# Processor.net
KiCad netlist of a schematic drawn in Altium Designer
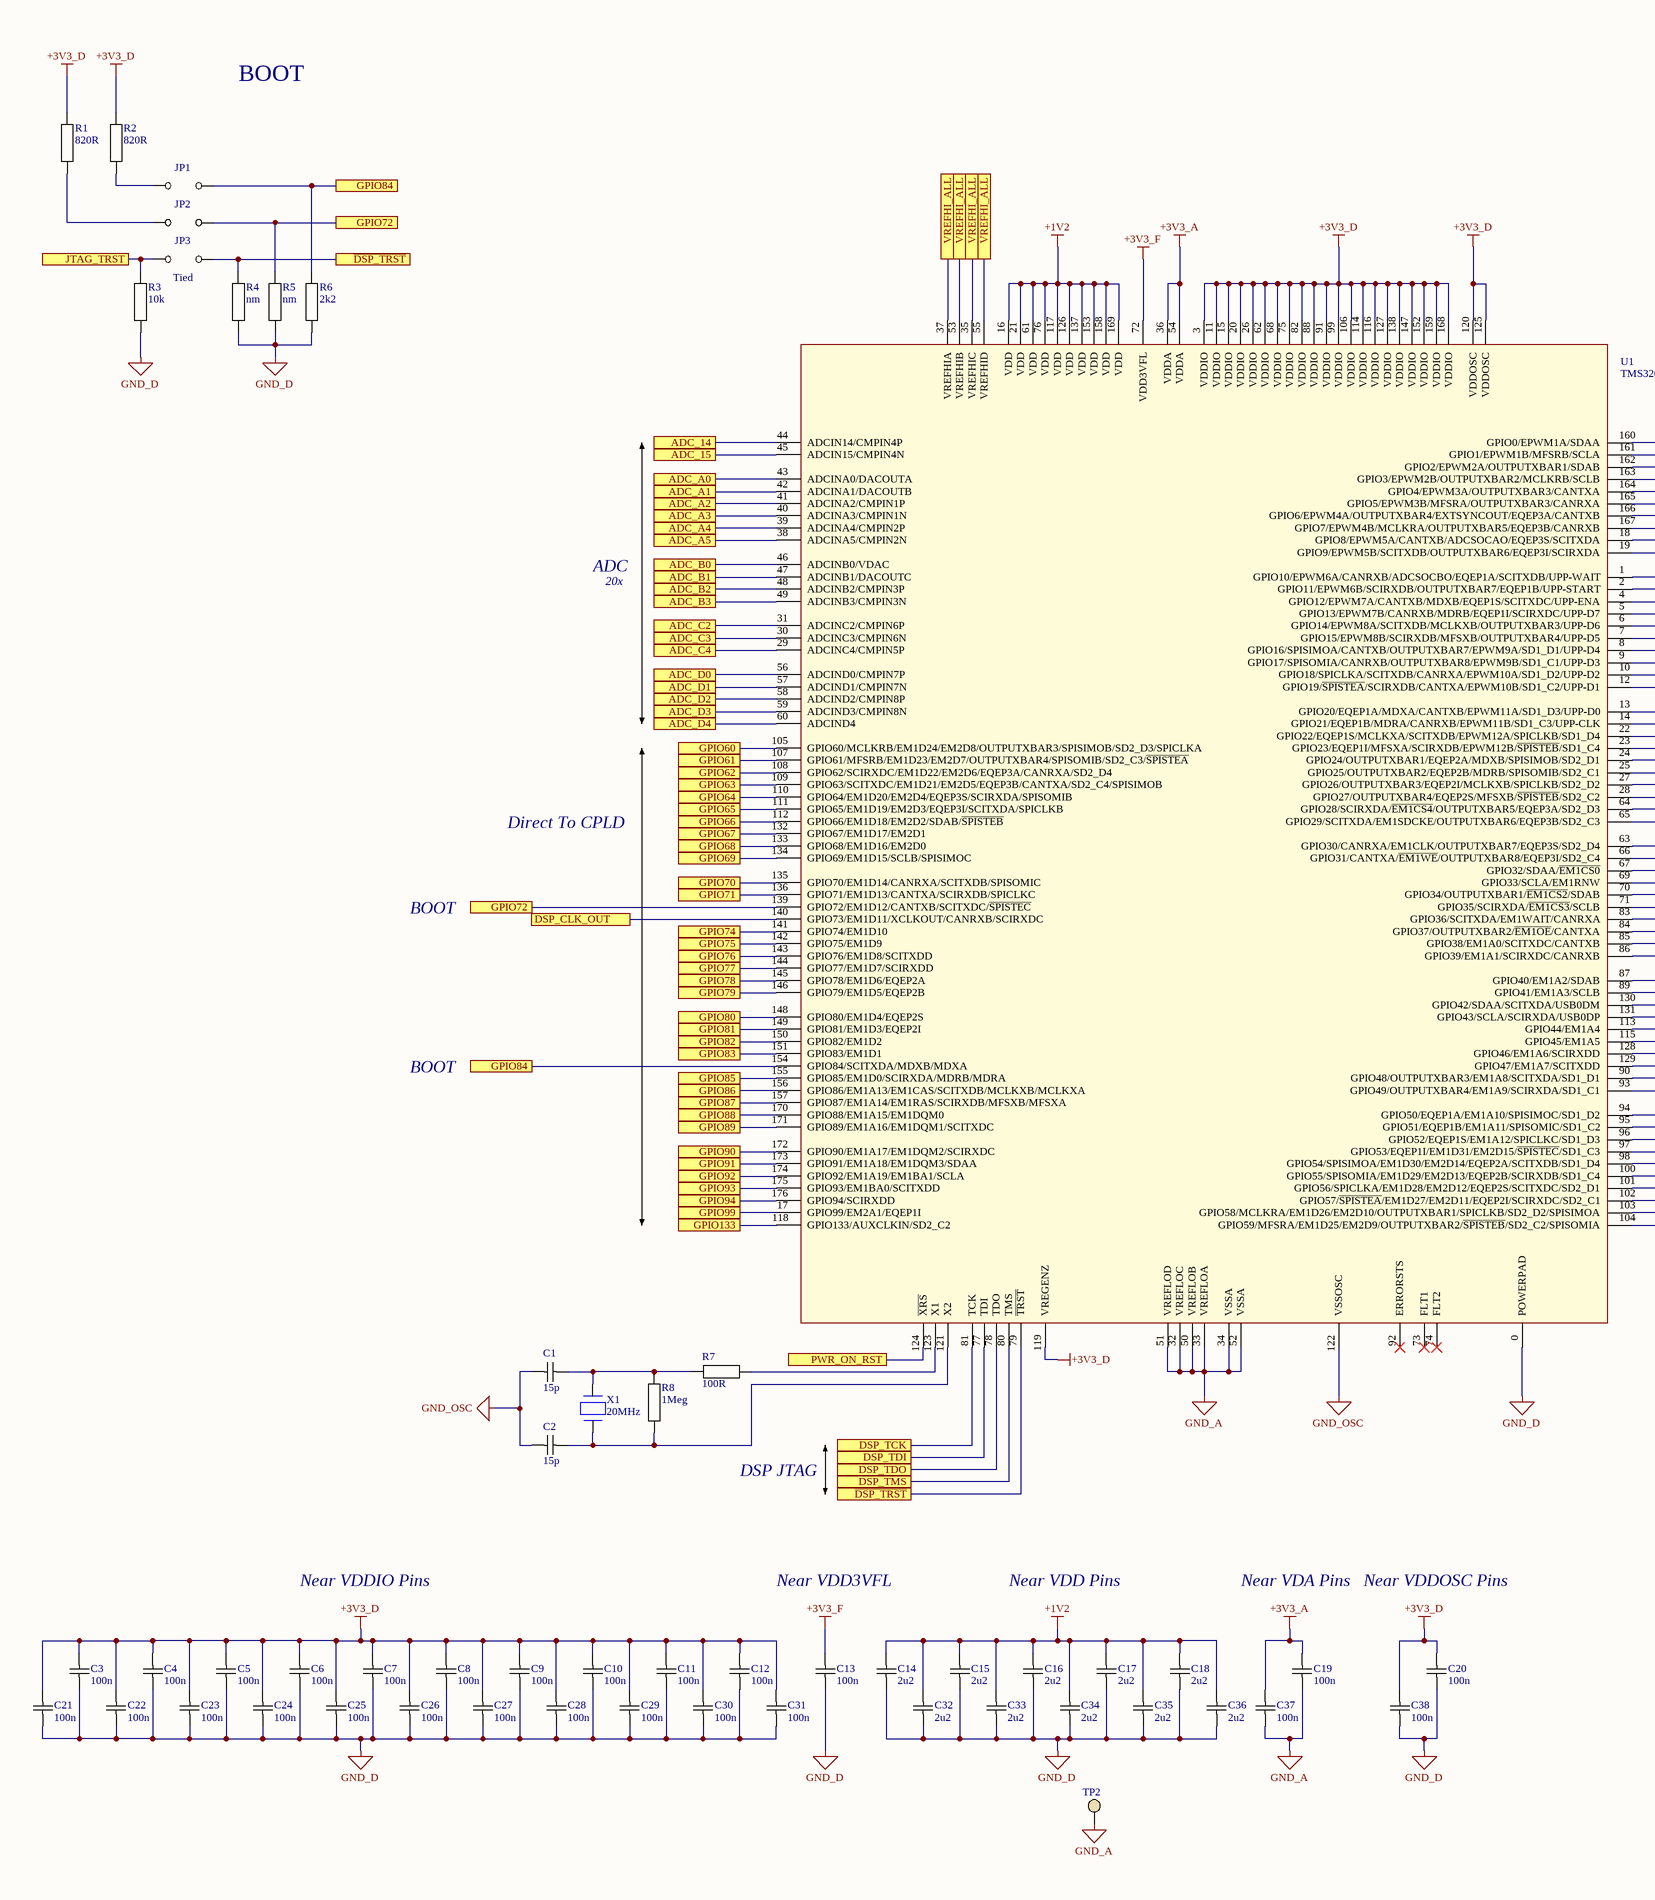
[diagram p0: Processor.SchDoc, left]
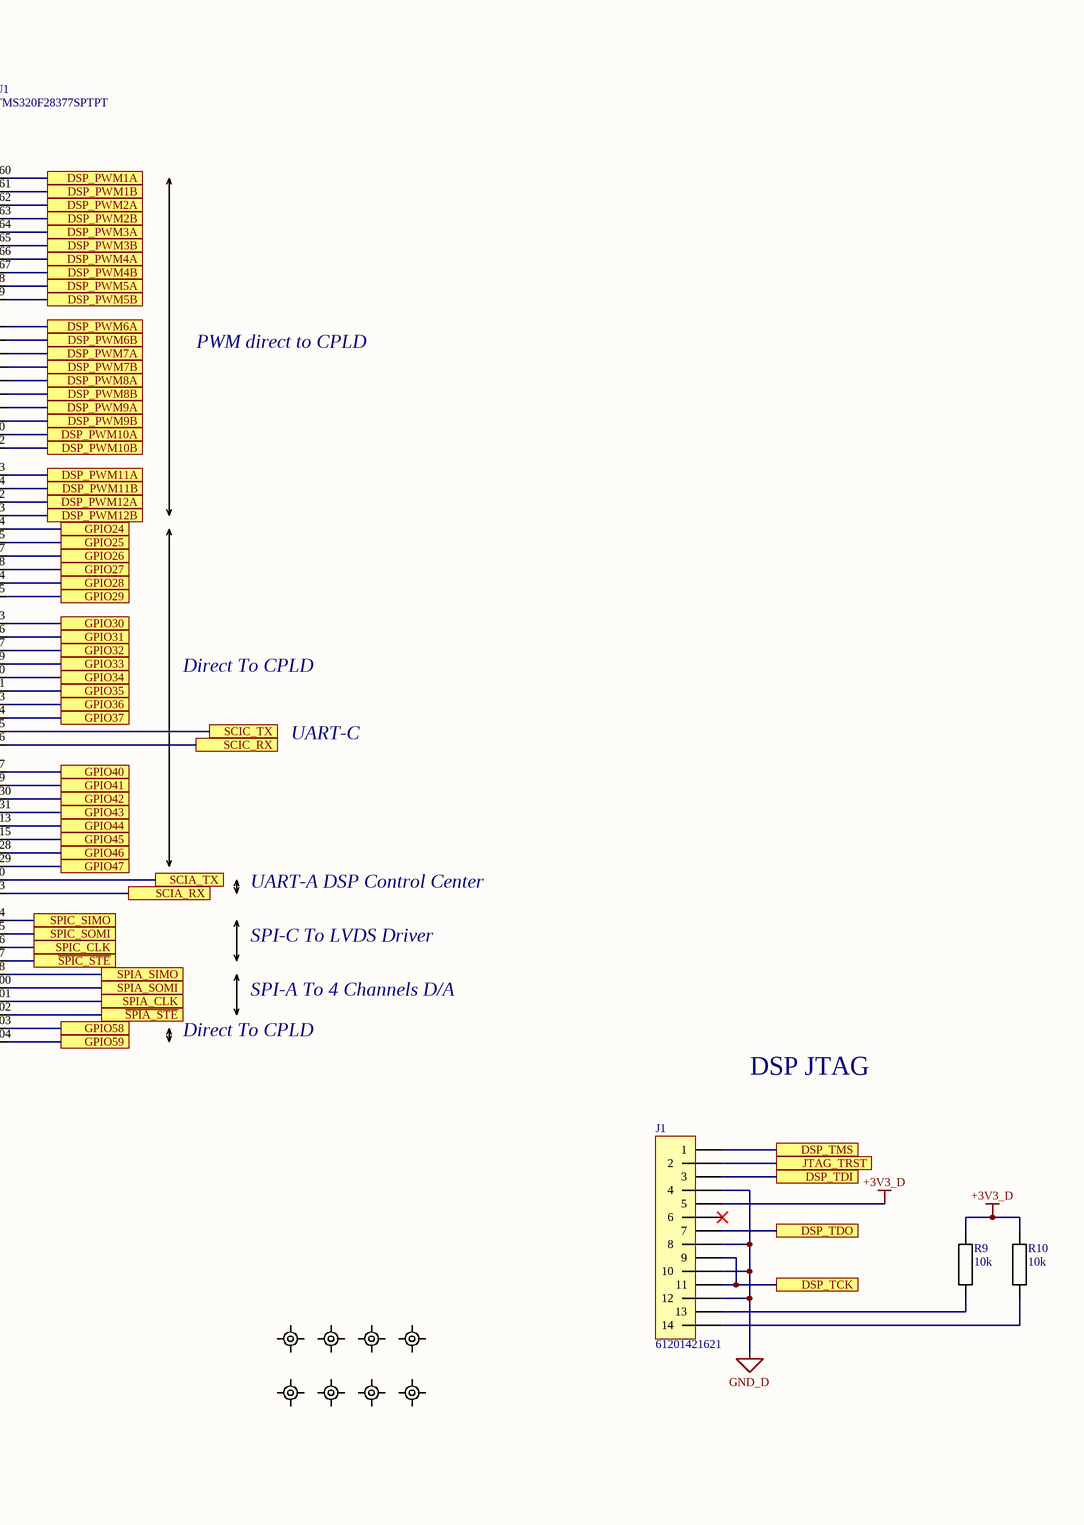
[diagram p1: Processor.SchDoc, right]

(export (version "E")
  (design (tool "Eeschema 10.0.6"))
  (components
    (comp (ref "C1")
      (value "15p")
      (footprint "CAPACITOR 1608 REFLOW")
      (description "Capacitor X7R 10% 50V 1608(0603)")
      (libsource (lib "Capacitor") (part "Capacitor"))
    )
    (comp (ref "C2")
      (value "15p")
      (footprint "CAPACITOR 1608 REFLOW")
      (description "Capacitor X7R 10% 50V 1608(0603)")
      (libsource (lib "Capacitor") (part "Capacitor"))
    )
    (comp (ref "C3")
      (value "100n")
      (footprint "CAPACITOR 1608 REFLOW")
      (description "Capacitor X7R 10% 50V 1608(0603)")
      (libsource (lib "Capacitor") (part "Capacitor"))
    )
    (comp (ref "C4")
      (value "100n")
      (footprint "CAPACITOR 1608 REFLOW")
      (description "Capacitor X7R 10% 50V 1608(0603)")
      (libsource (lib "Capacitor") (part "Capacitor"))
    )
    (comp (ref "C5")
      (value "100n")
      (footprint "CAPACITOR 1608 REFLOW")
      (description "Capacitor X7R 10% 50V 1608(0603)")
      (libsource (lib "Capacitor") (part "Capacitor"))
    )
    (comp (ref "C6")
      (value "100n")
      (footprint "CAPACITOR 1608 REFLOW")
      (description "Capacitor X7R 10% 50V 1608(0603)")
      (libsource (lib "Capacitor") (part "Capacitor"))
    )
    (comp (ref "C7")
      (value "100n")
      (footprint "CAPACITOR 1608 REFLOW")
      (description "Capacitor X7R 10% 50V 1608(0603)")
      (libsource (lib "Capacitor") (part "Capacitor"))
    )
    (comp (ref "C8")
      (value "100n")
      (footprint "CAPACITOR 1608 REFLOW")
      (description "Capacitor X7R 10% 50V 1608(0603)")
      (libsource (lib "Capacitor") (part "Capacitor"))
    )
    (comp (ref "C9")
      (value "100n")
      (footprint "CAPACITOR 1608 REFLOW")
      (description "Capacitor X7R 10% 50V 1608(0603)")
      (libsource (lib "Capacitor") (part "Capacitor"))
    )
    (comp (ref "C10")
      (value "100n")
      (footprint "CAPACITOR 1608 REFLOW")
      (description "Capacitor X7R 10% 50V 1608(0603)")
      (libsource (lib "Capacitor") (part "Capacitor"))
    )
    (comp (ref "C11")
      (value "100n")
      (footprint "CAPACITOR 1608 REFLOW")
      (description "Capacitor X7R 10% 50V 1608(0603)")
      (libsource (lib "Capacitor") (part "Capacitor"))
    )
    (comp (ref "C12")
      (value "100n")
      (footprint "CAPACITOR 1608 REFLOW")
      (description "Capacitor X7R 10% 50V 1608(0603)")
      (libsource (lib "Capacitor") (part "Capacitor"))
    )
    (comp (ref "C13")
      (value "100n")
      (footprint "CAPACITOR 1608 REFLOW")
      (description "Capacitor X7R 10% 50V 1608(0603)")
      (libsource (lib "Capacitor") (part "Capacitor"))
    )
    (comp (ref "C14")
      (value "2u2")
      (footprint "CAPACITOR 1608 REFLOW")
      (description "Capacitor X7R 10% 10V 1608(0603)")
      (libsource (lib "Capacitor") (part "Capacitor"))
    )
    (comp (ref "C15")
      (value "2u2")
      (footprint "CAPACITOR 1608 REFLOW")
      (description "Capacitor X7R 10% 10V 1608(0603)")
      (libsource (lib "Capacitor") (part "Capacitor"))
    )
    (comp (ref "C16")
      (value "2u2")
      (footprint "CAPACITOR 1608 REFLOW")
      (description "Capacitor X7R 10% 10V 1608(0603)")
      (libsource (lib "Capacitor") (part "Capacitor"))
    )
    (comp (ref "C17")
      (value "2u2")
      (footprint "CAPACITOR 1608 REFLOW")
      (description "Capacitor X7R 10% 10V 1608(0603)")
      (libsource (lib "Capacitor") (part "Capacitor"))
    )
    (comp (ref "C18")
      (value "2u2")
      (footprint "CAPACITOR 1608 REFLOW")
      (description "Capacitor X7R 10% 10V 1608(0603)")
      (libsource (lib "Capacitor") (part "Capacitor"))
    )
    (comp (ref "C19")
      (value "100n")
      (footprint "CAPACITOR 1608 REFLOW")
      (description "Capacitor X7R 10% 50V 1608(0603)")
      (libsource (lib "Capacitor") (part "Capacitor"))
    )
    (comp (ref "C20")
      (value "100n")
      (footprint "CAPACITOR 1608 REFLOW")
      (description "Capacitor X7R 10% 50V 1608(0603)")
      (libsource (lib "Capacitor") (part "Capacitor"))
    )
    (comp (ref "C21")
      (value "100n")
      (footprint "CAPACITOR 1608 REFLOW")
      (description "Capacitor X7R 10% 50V 1608(0603)")
      (libsource (lib "Capacitor") (part "Capacitor"))
    )
    (comp (ref "C22")
      (value "100n")
      (footprint "CAPACITOR 1608 REFLOW")
      (description "Capacitor X7R 10% 50V 1608(0603)")
      (libsource (lib "Capacitor") (part "Capacitor"))
    )
    (comp (ref "C23")
      (value "100n")
      (footprint "CAPACITOR 1608 REFLOW")
      (description "Capacitor X7R 10% 50V 1608(0603)")
      (libsource (lib "Capacitor") (part "Capacitor"))
    )
    (comp (ref "C24")
      (value "100n")
      (footprint "CAPACITOR 1608 REFLOW")
      (description "Capacitor X7R 10% 50V 1608(0603)")
      (libsource (lib "Capacitor") (part "Capacitor"))
    )
    (comp (ref "C25")
      (value "100n")
      (footprint "CAPACITOR 1608 REFLOW")
      (description "Capacitor X7R 10% 50V 1608(0603)")
      (libsource (lib "Capacitor") (part "Capacitor"))
    )
    (comp (ref "C26")
      (value "100n")
      (footprint "CAPACITOR 1608 REFLOW")
      (description "Capacitor X7R 10% 50V 1608(0603)")
      (libsource (lib "Capacitor") (part "Capacitor"))
    )
    (comp (ref "C27")
      (value "100n")
      (footprint "CAPACITOR 1608 REFLOW")
      (description "Capacitor X7R 10% 50V 1608(0603)")
      (libsource (lib "Capacitor") (part "Capacitor"))
    )
    (comp (ref "C28")
      (value "100n")
      (footprint "CAPACITOR 1608 REFLOW")
      (description "Capacitor X7R 10% 50V 1608(0603)")
      (libsource (lib "Capacitor") (part "Capacitor"))
    )
    (comp (ref "C29")
      (value "100n")
      (footprint "CAPACITOR 1608 REFLOW")
      (description "Capacitor X7R 10% 50V 1608(0603)")
      (libsource (lib "Capacitor") (part "Capacitor"))
    )
    (comp (ref "C30")
      (value "100n")
      (footprint "CAPACITOR 1608 REFLOW")
      (description "Capacitor X7R 10% 50V 1608(0603)")
      (libsource (lib "Capacitor") (part "Capacitor"))
    )
    (comp (ref "C31")
      (value "100n")
      (footprint "CAPACITOR 1608 REFLOW")
      (description "Capacitor X7R 10% 50V 1608(0603)")
      (libsource (lib "Capacitor") (part "Capacitor"))
    )
    (comp (ref "C32")
      (value "2u2")
      (footprint "CAPACITOR 1608 REFLOW")
      (description "Capacitor X7R 10% 10V 1608(0603)")
      (libsource (lib "Capacitor") (part "Capacitor"))
    )
    (comp (ref "C33")
      (value "2u2")
      (footprint "CAPACITOR 1608 REFLOW")
      (description "Capacitor X7R 10% 10V 1608(0603)")
      (libsource (lib "Capacitor") (part "Capacitor"))
    )
    (comp (ref "C34")
      (value "2u2")
      (footprint "CAPACITOR 1608 REFLOW")
      (description "Capacitor X7R 10% 10V 1608(0603)")
      (libsource (lib "Capacitor") (part "Capacitor"))
    )
    (comp (ref "C35")
      (value "2u2")
      (footprint "CAPACITOR 1608 REFLOW")
      (description "Capacitor X7R 10% 10V 1608(0603)")
      (libsource (lib "Capacitor") (part "Capacitor"))
    )
    (comp (ref "C36")
      (value "2u2")
      (footprint "CAPACITOR 1608 REFLOW")
      (description "Capacitor X7R 10% 10V 1608(0603)")
      (libsource (lib "Capacitor") (part "Capacitor"))
    )
    (comp (ref "C37")
      (value "100n")
      (footprint "CAPACITOR 1608 REFLOW")
      (description "Capacitor X7R 10% 50V 1608(0603)")
      (libsource (lib "Capacitor") (part "Capacitor"))
    )
    (comp (ref "C38")
      (value "100n")
      (footprint "CAPACITOR 1608 REFLOW")
      (description "Capacitor X7R 10% 50V 1608(0603)")
      (libsource (lib "Capacitor") (part "Capacitor"))
    )
    (comp (ref "J1")
      (value "61201421621")
      (footprint "FlatCable2x7 2.54MM Straight TH")
      (description "FlatCable2x7")
      (fields (field (name "MANUFACTURER") "Wurth Elektronik"))
      (libsource (lib "Connector") (part "FlatCable2x7"))
    )
    (comp (ref "JP1")
      (value "Tied")
      (footprint "JUMPER2 SMD 1608")
      (description "JUMPER 2 POS")
      (libsource (lib "Jumper") (part "JUMPER 2 POS"))
    )
    (comp (ref "JP2")
      (value "Tied")
      (footprint "JUMPER2 SMD 1608")
      (description "JUMPER 2 POS")
      (libsource (lib "Jumper") (part "JUMPER 2 POS"))
    )
    (comp (ref "JP3")
      (value "Tied")
      (footprint "JUMPER2 SMD 1608")
      (description "JUMPER 2 POS")
      (libsource (lib "Jumper") (part "JUMPER 2 POS"))
    )
    (comp (ref "R1")
      (value "820R")
      (footprint "RESISTOR 1608 REFLOW")
      (description "Resistor 1% 50V 100mW 1608(0603)")
      (libsource (lib "Resistor") (part "Resistor"))
    )
    (comp (ref "R2")
      (value "820R")
      (footprint "RESISTOR 1608 REFLOW")
      (description "Resistor 1% 50V 100mW 1608(0603)")
      (libsource (lib "Resistor") (part "Resistor"))
    )
    (comp (ref "R3")
      (value "10k")
      (footprint "RESISTOR 1608 REFLOW")
      (description "Resistor 1% 50V 100mW 1608(0603)")
      (libsource (lib "Resistor") (part "Resistor"))
    )
    (comp (ref "R4")
      (value "nm")
      (footprint "RESISTOR 1608 REFLOW")
      (description "Resistor 1% 50V 100mW 1608(0603)")
      (libsource (lib "Resistor") (part "Resistor"))
    )
    (comp (ref "R5")
      (value "nm")
      (footprint "RESISTOR 1608 REFLOW")
      (description "Resistor 1% 50V 100mW 1608(0603)")
      (libsource (lib "Resistor") (part "Resistor"))
    )
    (comp (ref "R6")
      (value "2k2")
      (footprint "RESISTOR 1608 REFLOW")
      (description "Resistor 1% 50V 100mW 1608(0603)")
      (libsource (lib "Resistor") (part "Resistor"))
    )
    (comp (ref "R7")
      (value "100R")
      (footprint "RESISTOR 1608 REFLOW")
      (description "Resistor 1% 50V 100mW 1608(0603)")
      (libsource (lib "Resistor") (part "Resistor"))
    )
    (comp (ref "R8")
      (value "1Meg")
      (footprint "RESISTOR 1608 REFLOW")
      (description "Resistor 1% 50V 100mW 1608(0603)")
      (libsource (lib "Resistor") (part "Resistor"))
    )
    (comp (ref "R9")
      (value "10k")
      (footprint "RESISTOR 1608 REFLOW")
      (description "Resistor 1% 50V 100mW 1608(0603)")
      (libsource (lib "Resistor") (part "Resistor"))
    )
    (comp (ref "R10")
      (value "10k")
      (footprint "RESISTOR 1608 REFLOW")
      (description "Resistor 1% 50V 100mW 1608(0603)")
      (libsource (lib "Resistor") (part "Resistor"))
    )
    (comp (ref "TP2")
      (value "*")
      (footprint "Test Point Keystone Miniature BLACK")
      (description "Test Point")
      (libsource (lib "Testpoint") (part "Test Point"))
    )
    (comp (ref "U1")
      (value "TMS320F28377SPTPT")
      (footprint "PQFP176 P0.5 C24.2X24.2 H1.5")
      (description "TMS320F28377S-176P")
      (fields (field (name "MANUFACTURER") "Texas Instruments"))
      (libsource (lib "Processor") (part "TMS320F28377S-176P"))
    )
    (comp (ref "X1")
      (value "20MHz")
      (footprint "Quartz HC49/4H SMX")
      (description "Quartz HC49/4H SMX")
      (libsource (lib "Oscillator") (part "Quartz HC49/4H SMX"))
    )
    (comp (ref "Z1")
      (value "1 - 3")
      (footprint "FIDUCIAL")
      (description "FIDUCIAL Din 1mm Dout 3mm")
      (libsource (lib "Mechanic") (part "FIDUCIAL"))
    )
    (comp (ref "Z2")
      (value "1 - 3")
      (footprint "FIDUCIAL")
      (description "FIDUCIAL Din 1mm Dout 3mm")
      (libsource (lib "Mechanic") (part "FIDUCIAL"))
    )
    (comp (ref "Z3")
      (value "1 - 3")
      (footprint "FIDUCIAL")
      (description "FIDUCIAL Din 1mm Dout 3mm")
      (libsource (lib "Mechanic") (part "FIDUCIAL"))
    )
    (comp (ref "Z4")
      (value "1 - 3")
      (footprint "FIDUCIAL")
      (description "FIDUCIAL Din 1mm Dout 3mm")
      (libsource (lib "Mechanic") (part "FIDUCIAL"))
    )
    (comp (ref "Z5")
      (value "1 - 3")
      (footprint "FIDUCIAL")
      (description "FIDUCIAL Din 1mm Dout 3mm")
      (libsource (lib "Mechanic") (part "FIDUCIAL"))
    )
    (comp (ref "Z6")
      (value "1 - 3")
      (footprint "FIDUCIAL")
      (description "FIDUCIAL Din 1mm Dout 3mm")
      (libsource (lib "Mechanic") (part "FIDUCIAL"))
    )
    (comp (ref "Z7")
      (value "1 - 3")
      (footprint "FIDUCIAL")
      (description "FIDUCIAL Din 1mm Dout 3mm")
      (libsource (lib "Mechanic") (part "FIDUCIAL"))
    )
    (comp (ref "Z8")
      (value "1 - 3")
      (footprint "FIDUCIAL")
      (description "FIDUCIAL Din 1mm Dout 3mm")
      (libsource (lib "Mechanic") (part "FIDUCIAL"))
    )
  )
  (nets
    (net (code "1") (name "+1V2") (class "Default")
      (node (ref "C14") (pin "2") (pinfunction "2_2") (pintype "passive"))
      (node (ref "C15") (pin "2") (pinfunction "2_2") (pintype "passive"))
      (node (ref "C16") (pin "2") (pinfunction "2_2") (pintype "passive"))
      (node (ref "C17") (pin "2") (pinfunction "2_2") (pintype "passive"))
      (node (ref "C18") (pin "2") (pinfunction "2_2") (pintype "passive"))
      (node (ref "C32") (pin "2") (pinfunction "2_2") (pintype "passive"))
      (node (ref "C33") (pin "2") (pinfunction "2_2") (pintype "passive"))
      (node (ref "C34") (pin "2") (pinfunction "2_2") (pintype "passive"))
      (node (ref "C35") (pin "2") (pinfunction "2_2") (pintype "passive"))
      (node (ref "C36") (pin "2") (pinfunction "2_2") (pintype "passive"))
      (node (ref "U1") (pin "117") (pinfunction "VDD_117") (pintype "passive"))
      (node (ref "U1") (pin "126") (pinfunction "VDD_126") (pintype "passive"))
      (node (ref "U1") (pin "137") (pinfunction "VDD_137") (pintype "passive"))
      (node (ref "U1") (pin "153") (pinfunction "VDD_153") (pintype "passive"))
      (node (ref "U1") (pin "158") (pinfunction "VDD_158") (pintype "passive"))
      (node (ref "U1") (pin "16") (pinfunction "VDD_16") (pintype "passive"))
      (node (ref "U1") (pin "169") (pinfunction "VDD_169") (pintype "passive"))
      (node (ref "U1") (pin "21") (pinfunction "VDD_21") (pintype "passive"))
      (node (ref "U1") (pin "61") (pinfunction "VDD_61") (pintype "passive"))
      (node (ref "U1") (pin "76") (pinfunction "VDD_76") (pintype "passive"))
    )
    (net (code "2") (name "+3V3_A") (class "Default")
      (node (ref "C19") (pin "2") (pinfunction "2_2") (pintype "passive"))
      (node (ref "C37") (pin "2") (pinfunction "2_2") (pintype "passive"))
      (node (ref "U1") (pin "36") (pinfunction "VDDA_36") (pintype "passive"))
      (node (ref "U1") (pin "54") (pinfunction "VDDA_54") (pintype "passive"))
    )
    (net (code "3") (name "+3V3_D") (class "Default")
      (node (ref "C10") (pin "2") (pinfunction "2_2") (pintype "passive"))
      (node (ref "C11") (pin "2") (pinfunction "2_2") (pintype "passive"))
      (node (ref "C12") (pin "2") (pinfunction "2_2") (pintype "passive"))
      (node (ref "C20") (pin "2") (pinfunction "2_2") (pintype "passive"))
      (node (ref "C21") (pin "2") (pinfunction "2_2") (pintype "passive"))
      (node (ref "C22") (pin "2") (pinfunction "2_2") (pintype "passive"))
      (node (ref "C23") (pin "2") (pinfunction "2_2") (pintype "passive"))
      (node (ref "C24") (pin "2") (pinfunction "2_2") (pintype "passive"))
      (node (ref "C25") (pin "2") (pinfunction "2_2") (pintype "passive"))
      (node (ref "C26") (pin "2") (pinfunction "2_2") (pintype "passive"))
      (node (ref "C27") (pin "2") (pinfunction "2_2") (pintype "passive"))
      (node (ref "C28") (pin "2") (pinfunction "2_2") (pintype "passive"))
      (node (ref "C29") (pin "2") (pinfunction "2_2") (pintype "passive"))
      (node (ref "C3") (pin "2") (pinfunction "2_2") (pintype "passive"))
      (node (ref "C30") (pin "2") (pinfunction "2_2") (pintype "passive"))
      (node (ref "C31") (pin "2") (pinfunction "2_2") (pintype "passive"))
      (node (ref "C38") (pin "2") (pinfunction "2_2") (pintype "passive"))
      (node (ref "C4") (pin "2") (pinfunction "2_2") (pintype "passive"))
      (node (ref "C5") (pin "2") (pinfunction "2_2") (pintype "passive"))
      (node (ref "C6") (pin "2") (pinfunction "2_2") (pintype "passive"))
      (node (ref "C7") (pin "2") (pinfunction "2_2") (pintype "passive"))
      (node (ref "C8") (pin "2") (pinfunction "2_2") (pintype "passive"))
      (node (ref "C9") (pin "2") (pinfunction "2_2") (pintype "passive"))
      (node (ref "J1") (pin "5") (pinfunction "5_5") (pintype "passive"))
      (node (ref "R1") (pin "2") (pinfunction "2_2") (pintype "passive"))
      (node (ref "R10") (pin "2") (pinfunction "2_2") (pintype "passive"))
      (node (ref "R2") (pin "2") (pinfunction "2_2") (pintype "passive"))
      (node (ref "R9") (pin "2") (pinfunction "2_2") (pintype "passive"))
      (node (ref "U1") (pin "106") (pinfunction "VDDIO_106") (pintype "passive"))
      (node (ref "U1") (pin "11") (pinfunction "VDDIO_11") (pintype "passive"))
      (node (ref "U1") (pin "114") (pinfunction "VDDIO_114") (pintype "passive"))
      (node (ref "U1") (pin "116") (pinfunction "VDDIO_116") (pintype "passive"))
      (node (ref "U1") (pin "119") (pinfunction "VREGENZ_119") (pintype "passive"))
      (node (ref "U1") (pin "120") (pinfunction "VDDOSC_120") (pintype "passive"))
      (node (ref "U1") (pin "125") (pinfunction "VDDOSC_125") (pintype "passive"))
      (node (ref "U1") (pin "127") (pinfunction "VDDIO_127") (pintype "passive"))
      (node (ref "U1") (pin "138") (pinfunction "VDDIO_138") (pintype "passive"))
      (node (ref "U1") (pin "147") (pinfunction "VDDIO_147") (pintype "passive"))
      (node (ref "U1") (pin "15") (pinfunction "VDDIO_15") (pintype "passive"))
      (node (ref "U1") (pin "152") (pinfunction "VDDIO_152") (pintype "passive"))
      (node (ref "U1") (pin "159") (pinfunction "VDDIO_159") (pintype "passive"))
      (node (ref "U1") (pin "168") (pinfunction "VDDIO_168") (pintype "passive"))
      (node (ref "U1") (pin "20") (pinfunction "VDDIO_20") (pintype "passive"))
      (node (ref "U1") (pin "26") (pinfunction "VDDIO_26") (pintype "passive"))
      (node (ref "U1") (pin "3") (pinfunction "VDDIO_3") (pintype "passive"))
      (node (ref "U1") (pin "62") (pinfunction "VDDIO_62") (pintype "passive"))
      (node (ref "U1") (pin "68") (pinfunction "VDDIO_68") (pintype "passive"))
      (node (ref "U1") (pin "75") (pinfunction "VDDIO_75") (pintype "passive"))
      (node (ref "U1") (pin "82") (pinfunction "VDDIO_82") (pintype "passive"))
      (node (ref "U1") (pin "88") (pinfunction "VDDIO_88") (pintype "passive"))
      (node (ref "U1") (pin "91") (pinfunction "VDDIO_91") (pintype "passive"))
      (node (ref "U1") (pin "99") (pinfunction "VDDIO_99") (pintype "passive"))
    )
    (net (code "4") (name "+3V3_F") (class "Default")
      (node (ref "C13") (pin "2") (pinfunction "2_2") (pintype "passive"))
      (node (ref "U1") (pin "72") (pinfunction "VDD3VFL_72") (pintype "passive"))
    )
    (net (code "5") (name "/ADC_14") (class "Default")
      (node (ref "U1") (pin "44") (pinfunction "ADCIN14/CMPIN4P_44") (pintype "passive"))
    )
    (net (code "6") (name "/ADC_15") (class "Default")
      (node (ref "U1") (pin "45") (pinfunction "ADCIN15/CMPIN4N_45") (pintype "passive"))
    )
    (net (code "7") (name "/ADC_A0") (class "Default")
      (node (ref "U1") (pin "43") (pinfunction "ADCINA0/DACOUTA_43") (pintype "passive"))
    )
    (net (code "8") (name "/ADC_A1") (class "Default")
      (node (ref "U1") (pin "42") (pinfunction "ADCINA1/DACOUTB_42") (pintype "passive"))
    )
    (net (code "9") (name "/ADC_A2") (class "Default")
      (node (ref "U1") (pin "41") (pinfunction "ADCINA2/CMPIN1P_41") (pintype "passive"))
    )
    (net (code "10") (name "/ADC_A3") (class "Default")
      (node (ref "U1") (pin "40") (pinfunction "ADCINA3/CMPIN1N_40") (pintype "passive"))
    )
    (net (code "11") (name "/ADC_A4") (class "Default")
      (node (ref "U1") (pin "39") (pinfunction "ADCINA4/CMPIN2P_39") (pintype "passive"))
    )
    (net (code "12") (name "/ADC_A5") (class "Default")
      (node (ref "U1") (pin "38") (pinfunction "ADCINA5/CMPIN2N_38") (pintype "passive"))
    )
    (net (code "13") (name "/ADC_B0") (class "Default")
      (node (ref "U1") (pin "46") (pinfunction "ADCINB0/VDAC_46") (pintype "passive"))
    )
    (net (code "14") (name "/ADC_B1") (class "Default")
      (node (ref "U1") (pin "47") (pinfunction "ADCINB1/DACOUTC_47") (pintype "passive"))
    )
    (net (code "15") (name "/ADC_B2") (class "Default")
      (node (ref "U1") (pin "48") (pinfunction "ADCINB2/CMPIN3P_48") (pintype "passive"))
    )
    (net (code "16") (name "/ADC_B3") (class "Default")
      (node (ref "U1") (pin "49") (pinfunction "ADCINB3/CMPIN3N_49") (pintype "passive"))
    )
    (net (code "17") (name "/ADC_C2") (class "Default")
      (node (ref "U1") (pin "31") (pinfunction "ADCINC2/CMPIN6P_31") (pintype "passive"))
    )
    (net (code "18") (name "/ADC_C3") (class "Default")
      (node (ref "U1") (pin "30") (pinfunction "ADCINC3/CMPIN6N_30") (pintype "passive"))
    )
    (net (code "19") (name "/ADC_C4") (class "Default")
      (node (ref "U1") (pin "29") (pinfunction "ADCINC4/CMPIN5P_29") (pintype "passive"))
    )
    (net (code "20") (name "/ADC_D0") (class "Default")
      (node (ref "U1") (pin "56") (pinfunction "ADCIND0/CMPIN7P_56") (pintype "passive"))
    )
    (net (code "21") (name "/ADC_D1") (class "Default")
      (node (ref "U1") (pin "57") (pinfunction "ADCIND1/CMPIN7N_57") (pintype "passive"))
    )
    (net (code "22") (name "/ADC_D2") (class "Default")
      (node (ref "U1") (pin "58") (pinfunction "ADCIND2/CMPIN8P_58") (pintype "passive"))
    )
    (net (code "23") (name "/ADC_D3") (class "Default")
      (node (ref "U1") (pin "59") (pinfunction "ADCIND3/CMPIN8N_59") (pintype "passive"))
    )
    (net (code "24") (name "/ADC_D4") (class "Default")
      (node (ref "U1") (pin "60") (pinfunction "ADCIND4_60") (pintype "passive"))
    )
    (net (code "25") (name "/DSP_CLK_OUT") (class "Default")
      (node (ref "U1") (pin "140") (pinfunction "GPIO73/EM1D11/XCLKOUT/CANRXB/SCIRXDC_140") (pintype "passive"))
    )
    (net (code "26") (name "/DSP_PWM1A") (class "Default")
      (node (ref "U1") (pin "160") (pinfunction "GPIO0/EPWM1A/SDAA_160") (pintype "passive"))
    )
    (net (code "27") (name "/DSP_PWM1B") (class "Default")
      (node (ref "U1") (pin "161") (pinfunction "GPIO1/EPWM1B/MFSRB/SCLA_161") (pintype "passive"))
    )
    (net (code "28") (name "/DSP_PWM2A") (class "Default")
      (node (ref "U1") (pin "162") (pinfunction "GPIO2/EPWM2A/OUTPUTXBAR1/SDAB_162") (pintype "passive"))
    )
    (net (code "29") (name "/DSP_PWM2B") (class "Default")
      (node (ref "U1") (pin "163") (pinfunction "GPIO3/EPWM2B/OUTPUTXBAR2/MCLKRB/SCLB_163") (pintype "passive"))
    )
    (net (code "30") (name "/DSP_PWM3A") (class "Default")
      (node (ref "U1") (pin "164") (pinfunction "GPIO4/EPWM3A/OUTPUTXBAR3/CANTXA_164") (pintype "passive"))
    )
    (net (code "31") (name "/DSP_PWM3B") (class "Default")
      (node (ref "U1") (pin "165") (pinfunction "GPIO5/EPWM3B/MFSRA/OUTPUTXBAR3/CANRXA_165") (pintype "passive"))
    )
    (net (code "32") (name "/DSP_PWM4A") (class "Default")
      (node (ref "U1") (pin "166") (pinfunction "GPIO6/EPWM4A/OUTPUTXBAR4/EXTSYNCOUT/EQEP3A/CANTXB_166") (pintype "passive"))
    )
    (net (code "33") (name "/DSP_PWM4B") (class "Default")
      (node (ref "U1") (pin "167") (pinfunction "GPIO7/EPWM4B/MCLKRA/OUTPUTXBAR5/EQEP3B/CANRXB_167") (pintype "passive"))
    )
    (net (code "34") (name "/DSP_PWM5A") (class "Default")
      (node (ref "U1") (pin "18") (pinfunction "GPIO8/EPWM5A/CANTXB/ADCSOCAO/EQEP3S/SCITXDA_18") (pintype "passive"))
    )
    (net (code "35") (name "/DSP_PWM5B") (class "Default")
      (node (ref "U1") (pin "19") (pinfunction "GPIO9/EPWM5B/SCITXDB/OUTPUTXBAR6/EQEP3I/SCIRXDA_19") (pintype "passive"))
    )
    (net (code "36") (name "/DSP_PWM6A") (class "Default")
      (node (ref "U1") (pin "1") (pinfunction "GPIO10/EPWM6A/CANRXB/ADCSOCBO/EQEP1A/SCITXDB/UPP-WAIT_1") (pintype "passive"))
    )
    (net (code "37") (name "/DSP_PWM6B") (class "Default")
      (node (ref "U1") (pin "2") (pinfunction "GPIO11/EPWM6B/SCIRXDB/OUTPUTXBAR7/EQEP1B/UPP-START_2") (pintype "passive"))
    )
    (net (code "38") (name "/DSP_PWM7A") (class "Default")
      (node (ref "U1") (pin "4") (pinfunction "GPIO12/EPWM7A/CANTXB/MDXB/EQEP1S/SCITXDC/UPP-ENA_4") (pintype "passive"))
    )
    (net (code "39") (name "/DSP_PWM7B") (class "Default")
      (node (ref "U1") (pin "5") (pinfunction "GPIO13/EPWM7B/CANRXB/MDRB/EQEP1I/SCIRXDC/UPP-D7_5") (pintype "passive"))
    )
    (net (code "40") (name "/DSP_PWM8A") (class "Default")
      (node (ref "U1") (pin "6") (pinfunction "GPIO14/EPWM8A/SCITXDB/MCLKXB/OUTPUTXBAR3/UPP-D6_6") (pintype "passive"))
    )
    (net (code "41") (name "/DSP_PWM8B") (class "Default")
      (node (ref "U1") (pin "7") (pinfunction "GPIO15/EPWM8B/SCIRXDB/MFSXB/OUTPUTXBAR4/UPP-D5_7") (pintype "passive"))
    )
    (net (code "42") (name "/DSP_PWM9A") (class "Default")
      (node (ref "U1") (pin "8") (pinfunction "GPIO16/SPISIMOA/CANTXB/OUTPUTXBAR7/EPWM9A/SD1_D1/UPP-D4_8") (pintype "passive"))
    )
    (net (code "43") (name "/DSP_PWM9B") (class "Default")
      (node (ref "U1") (pin "9") (pinfunction "GPIO17/SPISOMIA/CANRXB/OUTPUTXBAR8/EPWM9B/SD1_C1/UPP-D3_9") (pintype "passive"))
    )
    (net (code "44") (name "/DSP_PWM10A") (class "Default")
      (node (ref "U1") (pin "10") (pinfunction "GPIO18/SPICLKA/SCITXDB/CANRXA/EPWM10A/SD1_D2/UPP-D2_10") (pintype "passive"))
    )
    (net (code "45") (name "/DSP_PWM10B") (class "Default")
      (node (ref "U1") (pin "12") (pinfunction "GPIO19/~{SPISTEA}/SCIRXDB/CANTXA/EPWM10B/SD1_C2/UPP-D1_12") (pintype "passive"))
    )
    (net (code "46") (name "/DSP_PWM11A") (class "Default")
      (node (ref "U1") (pin "13") (pinfunction "GPIO20/EQEP1A/MDXA/CANTXB/EPWM11A/SD1_D3/UPP-D0_13") (pintype "passive"))
    )
    (net (code "47") (name "/DSP_PWM11B") (class "Default")
      (node (ref "U1") (pin "14") (pinfunction "GPIO21/EQEP1B/MDRA/CANRXB/EPWM11B/SD1_C3/UPP-CLK_14") (pintype "passive"))
    )
    (net (code "48") (name "/DSP_PWM12A") (class "Default")
      (node (ref "U1") (pin "22") (pinfunction "GPIO22/EQEP1S/MCLKXA/SCITXDB/EPWM12A/SPICLKB/SD1_D4_22") (pintype "passive"))
    )
    (net (code "49") (name "/DSP_PWM12B") (class "Default")
      (node (ref "U1") (pin "23") (pinfunction "GPIO23/EQEP1I/MFSXA/SCIRXDB/EPWM12B/~{SPISTEB}/SD1_C4_23") (pintype "passive"))
    )
    (net (code "50") (name "/DSP_TCK") (class "Default")
      (node (ref "J1") (pin "11") (pinfunction "11_11") (pintype "passive"))
      (node (ref "J1") (pin "9") (pinfunction "9_9") (pintype "passive"))
      (node (ref "U1") (pin "81") (pinfunction "TCK_81") (pintype "passive"))
    )
    (net (code "51") (name "/DSP_TDI") (class "Default")
      (node (ref "J1") (pin "3") (pinfunction "3_3") (pintype "passive"))
      (node (ref "U1") (pin "77") (pinfunction "TDI_77") (pintype "passive"))
    )
    (net (code "52") (name "/DSP_TDO") (class "Default")
      (node (ref "J1") (pin "7") (pinfunction "7_7") (pintype "passive"))
      (node (ref "U1") (pin "78") (pinfunction "TDO_78") (pintype "passive"))
    )
    (net (code "53") (name "/DSP_TMS") (class "Default")
      (node (ref "J1") (pin "1") (pinfunction "1_1") (pintype "passive"))
      (node (ref "U1") (pin "80") (pinfunction "TMS_80") (pintype "passive"))
    )
    (net (code "54") (name "/GPIO24") (class "Default")
      (node (ref "U1") (pin "24") (pinfunction "GPIO24/OUTPUTXBAR1/EQEP2A/MDXB/SPISIMOB/SD2_D1_24") (pintype "passive"))
    )
    (net (code "55") (name "/GPIO25") (class "Default")
      (node (ref "U1") (pin "25") (pinfunction "GPIO25/OUTPUTXBAR2/EQEP2B/MDRB/SPISOMIB/SD2_C1_25") (pintype "passive"))
    )
    (net (code "56") (name "/GPIO26") (class "Default")
      (node (ref "U1") (pin "27") (pinfunction "GPIO26/OUTPUTXBAR3/EQEP2I/MCLKXB/SPICLKB/SD2_D2_27") (pintype "passive"))
    )
    (net (code "57") (name "/GPIO27") (class "Default")
      (node (ref "U1") (pin "28") (pinfunction "GPIO27/OUTPUTXBAR4/EQEP2S/MFSXB/~{SPISTEB}/SD2_C2_28") (pintype "passive"))
    )
    (net (code "58") (name "/GPIO28") (class "Default")
      (node (ref "U1") (pin "64") (pinfunction "GPIO28/SCIRXDA/~{EM1CS4}/OUTPUTXBAR5/EQEP3A/SD2_D3_64") (pintype "passive"))
    )
    (net (code "59") (name "/GPIO29") (class "Default")
      (node (ref "U1") (pin "65") (pinfunction "GPIO29/SCITXDA/EM1SDCKE/OUTPUTXBAR6/EQEP3B/SD2_C3_65") (pintype "passive"))
    )
    (net (code "60") (name "/GPIO30") (class "Default")
      (node (ref "U1") (pin "63") (pinfunction "GPIO30/CANRXA/EM1CLK/OUTPUTXBAR7/EQEP3S/SD2_D4_63") (pintype "passive"))
    )
    (net (code "61") (name "/GPIO31") (class "Default")
      (node (ref "U1") (pin "66") (pinfunction "GPIO31/CANTXA/~{EM1WE}/OUTPUTXBAR8/EQEP3I/SD2_C4_66") (pintype "passive"))
    )
    (net (code "62") (name "/GPIO32") (class "Default")
      (node (ref "U1") (pin "67") (pinfunction "GPIO32/SDAA/~{EM1CS0}_67") (pintype "passive"))
    )
    (net (code "63") (name "/GPIO33") (class "Default")
      (node (ref "U1") (pin "69") (pinfunction "GPIO33/SCLA/EM1RNW_69") (pintype "passive"))
    )
    (net (code "64") (name "/GPIO34") (class "Default")
      (node (ref "U1") (pin "70") (pinfunction "GPIO34/OUTPUTXBAR1/~{EM1CS2}/SDAB_70") (pintype "passive"))
    )
    (net (code "65") (name "/GPIO35") (class "Default")
      (node (ref "U1") (pin "71") (pinfunction "GPIO35/SCIRXDA/~{EM1CS3}/SCLB_71") (pintype "passive"))
    )
    (net (code "66") (name "/GPIO36") (class "Default")
      (node (ref "U1") (pin "83") (pinfunction "GPIO36/SCITXDA/EM1WAIT/CANRXA_83") (pintype "passive"))
    )
    (net (code "67") (name "/GPIO37") (class "Default")
      (node (ref "U1") (pin "84") (pinfunction "GPIO37/OUTPUTXBAR2/~{EM1OE}/CANTXA_84") (pintype "passive"))
    )
    (net (code "68") (name "/GPIO40") (class "Default")
      (node (ref "U1") (pin "87") (pinfunction "GPIO40/EM1A2/SDAB_87") (pintype "passive"))
    )
    (net (code "69") (name "/GPIO41") (class "Default")
      (node (ref "U1") (pin "89") (pinfunction "GPIO41/EM1A3/SCLB_89") (pintype "passive"))
    )
    (net (code "70") (name "/GPIO42") (class "Default")
      (node (ref "U1") (pin "130") (pinfunction "GPIO42/SDAA/SCITXDA/USB0DM_130") (pintype "passive"))
    )
    (net (code "71") (name "/GPIO43") (class "Default")
      (node (ref "U1") (pin "131") (pinfunction "GPIO43/SCLA/SCIRXDA/USB0DP_131") (pintype "passive"))
    )
    (net (code "72") (name "/GPIO44") (class "Default")
      (node (ref "U1") (pin "113") (pinfunction "GPIO44/EM1A4_113") (pintype "passive"))
    )
    (net (code "73") (name "/GPIO45") (class "Default")
      (node (ref "U1") (pin "115") (pinfunction "GPIO45/EM1A5_115") (pintype "passive"))
    )
    (net (code "74") (name "/GPIO46") (class "Default")
      (node (ref "U1") (pin "128") (pinfunction "GPIO46/EM1A6/SCIRXDD_128") (pintype "passive"))
    )
    (net (code "75") (name "/GPIO47") (class "Default")
      (node (ref "U1") (pin "129") (pinfunction "GPIO47/EM1A7/SCITXDD_129") (pintype "passive"))
    )
    (net (code "76") (name "/GPIO58") (class "Default")
      (node (ref "U1") (pin "103") (pinfunction "GPIO58/MCLKRA/EM1D26/EM2D10/OUTPUTXBAR1/SPICLKB/SD2_D2/SPISIMOA_103") (pintype "passive"))
    )
    (net (code "77") (name "/GPIO59") (class "Default")
      (node (ref "U1") (pin "104") (pinfunction "GPIO59/MFSRA/EM1D25/EM2D9/OUTPUTXBAR2/~{SPISTEB}/SD2_C2/SPISOMIA_104") (pintype "passive"))
    )
    (net (code "78") (name "/GPIO60") (class "Default")
      (node (ref "U1") (pin "105") (pinfunction "GPIO60/MCLKRB/EM1D24/EM2D8/OUTPUTXBAR3/SPISIMOB/SD2_D3/SPICLKA_105") (pintype "passive"))
    )
    (net (code "79") (name "/GPIO61") (class "Default")
      (node (ref "U1") (pin "107") (pinfunction "GPIO61/MFSRB/EM1D23/EM2D7/OUTPUTXBAR4/SPISOMIB/SD2_C3/~{SPISTEA}_107") (pintype "passive"))
    )
    (net (code "80") (name "/GPIO62") (class "Default")
      (node (ref "U1") (pin "108") (pinfunction "GPIO62/SCIRXDC/EM1D22/EM2D6/EQEP3A/CANRXA/SD2_D4_108") (pintype "passive"))
    )
    (net (code "81") (name "/GPIO63") (class "Default")
      (node (ref "U1") (pin "109") (pinfunction "GPIO63/SCITXDC/EM1D21/EM2D5/EQEP3B/CANTXA/SD2_C4/SPISIMOB_109") (pintype "passive"))
    )
    (net (code "82") (name "/GPIO64") (class "Default")
      (node (ref "U1") (pin "110") (pinfunction "GPIO64/EM1D20/EM2D4/EQEP3S/SCIRXDA/SPISOMIB_110") (pintype "passive"))
    )
    (net (code "83") (name "/GPIO65") (class "Default")
      (node (ref "U1") (pin "111") (pinfunction "GPIO65/EM1D19/EM2D3/EQEP3I/SCITXDA/SPICLKB_111") (pintype "passive"))
    )
    (net (code "84") (name "/GPIO66") (class "Default")
      (node (ref "U1") (pin "112") (pinfunction "GPIO66/EM1D18/EM2D2/SDAB/~{SPISTEB}_112") (pintype "passive"))
    )
    (net (code "85") (name "/GPIO67") (class "Default")
      (node (ref "U1") (pin "132") (pinfunction "GPIO67/EM1D17/EM2D1_132") (pintype "passive"))
    )
    (net (code "86") (name "/GPIO68") (class "Default")
      (node (ref "U1") (pin "133") (pinfunction "GPIO68/EM1D16/EM2D0_133") (pintype "passive"))
    )
    (net (code "87") (name "/GPIO69") (class "Default")
      (node (ref "U1") (pin "134") (pinfunction "GPIO69/EM1D15/SCLB/SPISIMOC_134") (pintype "passive"))
    )
    (net (code "88") (name "/GPIO70") (class "Default")
      (node (ref "U1") (pin "135") (pinfunction "GPIO70/EM1D14/CANRXA/SCITXDB/SPISOMIC_135") (pintype "passive"))
    )
    (net (code "89") (name "/GPIO71") (class "Default")
      (node (ref "U1") (pin "136") (pinfunction "GPIO71/EM1D13/CANTXA/SCIRXDB/SPICLKC_136") (pintype "passive"))
    )
    (net (code "90") (name "/GPIO72") (class "Default")
      (node (ref "JP2") (pin "2") (pinfunction "2_2") (pintype "passive"))
      (node (ref "R5") (pin "2") (pinfunction "2_2") (pintype "passive"))
      (node (ref "U1") (pin "139") (pinfunction "GPIO72/EM1D12/CANTXB/SCITXDC/~{SPISTEC}_139") (pintype "passive"))
    )
    (net (code "91") (name "/GPIO74") (class "Default")
      (node (ref "U1") (pin "141") (pinfunction "GPIO74/EM1D10_141") (pintype "passive"))
    )
    (net (code "92") (name "/GPIO75") (class "Default")
      (node (ref "U1") (pin "142") (pinfunction "GPIO75/EM1D9_142") (pintype "passive"))
    )
    (net (code "93") (name "/GPIO76") (class "Default")
      (node (ref "U1") (pin "143") (pinfunction "GPIO76/EM1D8/SCITXDD_143") (pintype "passive"))
    )
    (net (code "94") (name "/GPIO77") (class "Default")
      (node (ref "U1") (pin "144") (pinfunction "GPIO77/EM1D7/SCIRXDD_144") (pintype "passive"))
    )
    (net (code "95") (name "/GPIO78") (class "Default")
      (node (ref "U1") (pin "145") (pinfunction "GPIO78/EM1D6/EQEP2A_145") (pintype "passive"))
    )
    (net (code "96") (name "/GPIO79") (class "Default")
      (node (ref "U1") (pin "146") (pinfunction "GPIO79/EM1D5/EQEP2B_146") (pintype "passive"))
    )
    (net (code "97") (name "/GPIO80") (class "Default")
      (node (ref "U1") (pin "148") (pinfunction "GPIO80/EM1D4/EQEP2S_148") (pintype "passive"))
    )
    (net (code "98") (name "/GPIO81") (class "Default")
      (node (ref "U1") (pin "149") (pinfunction "GPIO81/EM1D3/EQEP2I_149") (pintype "passive"))
    )
    (net (code "99") (name "/GPIO82") (class "Default")
      (node (ref "U1") (pin "150") (pinfunction "GPIO82/EM1D2_150") (pintype "passive"))
    )
    (net (code "100") (name "/GPIO83") (class "Default")
      (node (ref "U1") (pin "151") (pinfunction "GPIO83/EM1D1_151") (pintype "passive"))
    )
    (net (code "101") (name "/GPIO84") (class "Default")
      (node (ref "JP1") (pin "2") (pinfunction "2_2") (pintype "passive"))
      (node (ref "R6") (pin "2") (pinfunction "2_2") (pintype "passive"))
      (node (ref "U1") (pin "154") (pinfunction "GPIO84/SCITXDA/MDXB/MDXA_154") (pintype "passive"))
    )
    (net (code "102") (name "/GPIO85") (class "Default")
      (node (ref "U1") (pin "155") (pinfunction "GPIO85/EM1D0/SCIRXDA/MDRB/MDRA_155") (pintype "passive"))
    )
    (net (code "103") (name "/GPIO86") (class "Default")
      (node (ref "U1") (pin "156") (pinfunction "GPIO86/EM1A13/EM1CAS/SCITXDB/MCLKXB/MCLKXA_156") (pintype "passive"))
    )
    (net (code "104") (name "/GPIO87") (class "Default")
      (node (ref "U1") (pin "157") (pinfunction "GPIO87/EM1A14/EM1RAS/SCIRXDB/MFSXB/MFSXA_157") (pintype "passive"))
    )
    (net (code "105") (name "/GPIO88") (class "Default")
      (node (ref "U1") (pin "170") (pinfunction "GPIO88/EM1A15/EM1DQM0_170") (pintype "passive"))
    )
    (net (code "106") (name "/GPIO89") (class "Default")
      (node (ref "U1") (pin "171") (pinfunction "GPIO89/EM1A16/EM1DQM1/SCITXDC_171") (pintype "passive"))
    )
    (net (code "107") (name "/GPIO90") (class "Default")
      (node (ref "U1") (pin "172") (pinfunction "GPIO90/EM1A17/EM1DQM2/SCIRXDC_172") (pintype "passive"))
    )
    (net (code "108") (name "/GPIO91") (class "Default")
      (node (ref "U1") (pin "173") (pinfunction "GPIO91/EM1A18/EM1DQM3/SDAA_173") (pintype "passive"))
    )
    (net (code "109") (name "/GPIO92") (class "Default")
      (node (ref "U1") (pin "174") (pinfunction "GPIO92/EM1A19/EM1BA1/SCLA_174") (pintype "passive"))
    )
    (net (code "110") (name "/GPIO93") (class "Default")
      (node (ref "U1") (pin "175") (pinfunction "GPIO93/EM1BA0/SCITXDD_175") (pintype "passive"))
    )
    (net (code "111") (name "/GPIO94") (class "Default")
      (node (ref "U1") (pin "176") (pinfunction "GPIO94/SCIRXDD_176") (pintype "passive"))
    )
    (net (code "112") (name "/GPIO99") (class "Default")
      (node (ref "U1") (pin "17") (pinfunction "GPIO99/EM2A1/EQEP1I_17") (pintype "passive"))
    )
    (net (code "113") (name "/GPIO133") (class "Default")
      (node (ref "U1") (pin "118") (pinfunction "GPIO133/AUXCLKIN/SD2_C2_118") (pintype "passive"))
    )
    (net (code "114") (name "/JTAG_TRST") (class "Default")
      (node (ref "J1") (pin "2") (pinfunction "2_2") (pintype "passive"))
      (node (ref "JP3") (pin "1") (pinfunction "1_1") (pintype "passive"))
      (node (ref "R3") (pin "2") (pinfunction "2_2") (pintype "passive"))
    )
    (net (code "115") (name "/PWR_ON_RST") (class "Default")
      (node (ref "U1") (pin "124") (pinfunction "~{XRS}_124") (pintype "passive"))
    )
    (net (code "116") (name "/SCIA_RX") (class "Default")
      (node (ref "U1") (pin "93") (pinfunction "GPIO49/OUTPUTXBAR4/EM1A9/SCIRXDA/SD1_C1_93") (pintype "passive"))
    )
    (net (code "117") (name "/SCIA_TX") (class "Default")
      (node (ref "U1") (pin "90") (pinfunction "GPIO48/OUTPUTXBAR3/EM1A8/SCITXDA/SD1_D1_90") (pintype "passive"))
    )
    (net (code "118") (name "/SCIC_RX") (class "Default")
      (node (ref "U1") (pin "86") (pinfunction "GPIO39/EM1A1/SCIRXDC/CANRXB_86") (pintype "passive"))
    )
    (net (code "119") (name "/SCIC_TX") (class "Default")
      (node (ref "U1") (pin "85") (pinfunction "GPIO38/EM1A0/SCITXDC/CANTXB_85") (pintype "passive"))
    )
    (net (code "120") (name "/SPIA_CLK") (class "Default")
      (node (ref "U1") (pin "101") (pinfunction "GPIO56/SPICLKA/EM1D28/EM2D12/EQEP2S/SCITXDC/SD2_D1_101") (pintype "passive"))
    )
    (net (code "121") (name "/SPIA_SIMO") (class "Default")
      (node (ref "U1") (pin "98") (pinfunction "GPIO54/SPISIMOA/EM1D30/EM2D14/EQEP2A/SCITXDB/SD1_D4_98") (pintype "passive"))
    )
    (net (code "122") (name "/SPIA_SOMI") (class "Default")
      (node (ref "U1") (pin "100") (pinfunction "GPIO55/SPISOMIA/EM1D29/EM2D13/EQEP2B/SCIRXDB/SD1_C4_100") (pintype "passive"))
    )
    (net (code "123") (name "/SPIC_CLK") (class "Default")
      (node (ref "U1") (pin "96") (pinfunction "GPIO52/EQEP1S/EM1A12/SPICLKC/SD1_D3_96") (pintype "passive"))
    )
    (net (code "124") (name "/SPIC_SIMO") (class "Default")
      (node (ref "U1") (pin "94") (pinfunction "GPIO50/EQEP1A/EM1A10/SPISIMOC/SD1_D2_94") (pintype "passive"))
    )
    (net (code "125") (name "/SPIC_SOMI") (class "Default")
      (node (ref "U1") (pin "95") (pinfunction "GPIO51/EQEP1B/EM1A11/SPISOMIC/SD1_C2_95") (pintype "passive"))
    )
    (net (code "126") (name "/VREFHI_ALL") (class "Default")
      (node (ref "U1") (pin "35") (pinfunction "VREFHIC_35") (pintype "passive"))
      (node (ref "U1") (pin "37") (pinfunction "VREFHIA_37") (pintype "passive"))
      (node (ref "U1") (pin "53") (pinfunction "VREFHIB_53") (pintype "passive"))
      (node (ref "U1") (pin "55") (pinfunction "VREFHID_55") (pintype "passive"))
    )
    (net (code "127") (name "/~{DSP_TRST}") (class "Default")
      (node (ref "JP3") (pin "2") (pinfunction "2_2") (pintype "passive"))
      (node (ref "R4") (pin "2") (pinfunction "2_2") (pintype "passive"))
      (node (ref "U1") (pin "79") (pinfunction "~{TRST}_79") (pintype "passive"))
    )
    (net (code "128") (name "/~{SPIA_STE}") (class "Default")
      (node (ref "U1") (pin "102") (pinfunction "GPIO57/~{SPISTEA}/EM1D27/EM2D11/EQEP2I/SCIRXDC/SD2_C1_102") (pintype "passive"))
    )
    (net (code "129") (name "/~{SPIC_STE}") (class "Default")
      (node (ref "U1") (pin "97") (pinfunction "GPIO53/EQEP1I/EM1D31/EM2D15/~{SPISTEC}/SD1_C3_97") (pintype "passive"))
    )
    (net (code "130") (name "GND_A") (class "Default")
      (node (ref "C19") (pin "1") (pinfunction "1_1") (pintype "passive"))
      (node (ref "C37") (pin "1") (pinfunction "1_1") (pintype "passive"))
      (node (ref "TP2") (pin "1") (pinfunction "1_1") (pintype "passive"))
      (node (ref "U1") (pin "32") (pinfunction "VREFLOC_32") (pintype "passive"))
      (node (ref "U1") (pin "33") (pinfunction "VREFLOA_33") (pintype "passive"))
      (node (ref "U1") (pin "34") (pinfunction "VSSA_34") (pintype "passive"))
      (node (ref "U1") (pin "50") (pinfunction "VREFLOB_50") (pintype "passive"))
      (node (ref "U1") (pin "51") (pinfunction "VREFLOD_51") (pintype "passive"))
      (node (ref "U1") (pin "52") (pinfunction "VSSA_52") (pintype "passive"))
    )
    (net (code "131") (name "GND_D") (class "Default")
      (node (ref "C10") (pin "1") (pinfunction "1_1") (pintype "passive"))
      (node (ref "C11") (pin "1") (pinfunction "1_1") (pintype "passive"))
      (node (ref "C12") (pin "1") (pinfunction "1_1") (pintype "passive"))
      (node (ref "C13") (pin "1") (pinfunction "1_1") (pintype "passive"))
      (node (ref "C14") (pin "1") (pinfunction "1_1") (pintype "passive"))
      (node (ref "C15") (pin "1") (pinfunction "1_1") (pintype "passive"))
      (node (ref "C16") (pin "1") (pinfunction "1_1") (pintype "passive"))
      (node (ref "C17") (pin "1") (pinfunction "1_1") (pintype "passive"))
      (node (ref "C18") (pin "1") (pinfunction "1_1") (pintype "passive"))
      (node (ref "C20") (pin "1") (pinfunction "1_1") (pintype "passive"))
      (node (ref "C21") (pin "1") (pinfunction "1_1") (pintype "passive"))
      (node (ref "C22") (pin "1") (pinfunction "1_1") (pintype "passive"))
      (node (ref "C23") (pin "1") (pinfunction "1_1") (pintype "passive"))
      (node (ref "C24") (pin "1") (pinfunction "1_1") (pintype "passive"))
      (node (ref "C25") (pin "1") (pinfunction "1_1") (pintype "passive"))
      (node (ref "C26") (pin "1") (pinfunction "1_1") (pintype "passive"))
      (node (ref "C27") (pin "1") (pinfunction "1_1") (pintype "passive"))
      (node (ref "C28") (pin "1") (pinfunction "1_1") (pintype "passive"))
      (node (ref "C29") (pin "1") (pinfunction "1_1") (pintype "passive"))
      (node (ref "C3") (pin "1") (pinfunction "1_1") (pintype "passive"))
      (node (ref "C30") (pin "1") (pinfunction "1_1") (pintype "passive"))
      (node (ref "C31") (pin "1") (pinfunction "1_1") (pintype "passive"))
      (node (ref "C32") (pin "1") (pinfunction "1_1") (pintype "passive"))
      (node (ref "C33") (pin "1") (pinfunction "1_1") (pintype "passive"))
      (node (ref "C34") (pin "1") (pinfunction "1_1") (pintype "passive"))
      (node (ref "C35") (pin "1") (pinfunction "1_1") (pintype "passive"))
      (node (ref "C36") (pin "1") (pinfunction "1_1") (pintype "passive"))
      (node (ref "C38") (pin "1") (pinfunction "1_1") (pintype "passive"))
      (node (ref "C4") (pin "1") (pinfunction "1_1") (pintype "passive"))
      (node (ref "C5") (pin "1") (pinfunction "1_1") (pintype "passive"))
      (node (ref "C6") (pin "1") (pinfunction "1_1") (pintype "passive"))
      (node (ref "C7") (pin "1") (pinfunction "1_1") (pintype "passive"))
      (node (ref "C8") (pin "1") (pinfunction "1_1") (pintype "passive"))
      (node (ref "C9") (pin "1") (pinfunction "1_1") (pintype "passive"))
      (node (ref "J1") (pin "10") (pinfunction "10_10") (pintype "passive"))
      (node (ref "J1") (pin "12") (pinfunction "12_12") (pintype "passive"))
      (node (ref "J1") (pin "4") (pinfunction "4_4") (pintype "passive"))
      (node (ref "J1") (pin "8") (pinfunction "8_8") (pintype "passive"))
      (node (ref "R3") (pin "1") (pinfunction "1_1") (pintype "passive"))
      (node (ref "R4") (pin "1") (pinfunction "1_1") (pintype "passive"))
      (node (ref "R5") (pin "1") (pinfunction "1_1") (pintype "passive"))
      (node (ref "R6") (pin "1") (pinfunction "1_1") (pintype "passive"))
      (node (ref "U1") (pin "0") (pinfunction "POWERPAD_0") (pintype "passive"))
    )
    (net (code "132") (name "GND_OSC") (class "Default")
      (node (ref "C1") (pin "1") (pinfunction "1_1") (pintype "passive"))
      (node (ref "C2") (pin "1") (pinfunction "1_1") (pintype "passive"))
      (node (ref "U1") (pin "122") (pinfunction "VSSOSC_122") (pintype "passive"))
    )
    (net (code "133") (name "Net-(C1-Pad2)") (class "Default")
      (node (ref "C1") (pin "2") (pinfunction "2_2") (pintype "passive"))
      (node (ref "R7") (pin "1") (pinfunction "1_1") (pintype "passive"))
      (node (ref "R8") (pin "2") (pinfunction "2_2") (pintype "passive"))
      (node (ref "X1") (pin "2") (pinfunction "2_2") (pintype "passive"))
    )
    (net (code "134") (name "Net-(J1-Pad13)") (class "Default")
      (node (ref "J1") (pin "13") (pinfunction "13_13") (pintype "passive"))
      (node (ref "R9") (pin "1") (pinfunction "1_1") (pintype "passive"))
    )
    (net (code "135") (name "Net-(J1-Pad14)") (class "Default")
      (node (ref "J1") (pin "14") (pinfunction "14_14") (pintype "passive"))
      (node (ref "R10") (pin "1") (pinfunction "1_1") (pintype "passive"))
    )
    (net (code "136") (name "Net-(JP1-Pad1)") (class "Default")
      (node (ref "JP1") (pin "1") (pinfunction "1_1") (pintype "passive"))
      (node (ref "R2") (pin "1") (pinfunction "1_1") (pintype "passive"))
    )
    (net (code "137") (name "Net-(JP2-Pad1)") (class "Default")
      (node (ref "JP2") (pin "1") (pinfunction "1_1") (pintype "passive"))
      (node (ref "R1") (pin "1") (pinfunction "1_1") (pintype "passive"))
    )
    (net (code "138") (name "Net-(U1-X1)") (class "Default")
      (node (ref "R7") (pin "2") (pinfunction "2_2") (pintype "passive"))
      (node (ref "U1") (pin "123") (pinfunction "X1_123") (pintype "passive"))
    )
    (net (code "139") (name "Net-(U1-X2)") (class "Default")
      (node (ref "C2") (pin "2") (pinfunction "2_2") (pintype "passive"))
      (node (ref "R8") (pin "1") (pinfunction "1_1") (pintype "passive"))
      (node (ref "U1") (pin "121") (pinfunction "X2_121") (pintype "passive"))
      (node (ref "X1") (pin "1") (pinfunction "1_1") (pintype "passive"))
    )
    (net (code "140") (name "unconnected-(J1-Pad6)") (class "Default")
      (node (ref "J1") (pin "6") (pinfunction "6_6") (pintype "passive+no_connect"))
    )
    (net (code "141") (name "unconnected-(U1-ERRORSTS-Pad92)") (class "Default")
      (node (ref "U1") (pin "92") (pinfunction "ERRORSTS_92") (pintype "passive+no_connect"))
    )
    (net (code "142") (name "unconnected-(U1-FLT1-Pad73)") (class "Default")
      (node (ref "U1") (pin "73") (pinfunction "FLT1_73") (pintype "passive+no_connect"))
    )
    (net (code "143") (name "unconnected-(U1-FLT2-Pad74)") (class "Default")
      (node (ref "U1") (pin "74") (pinfunction "FLT2_74") (pintype "passive+no_connect"))
    )
  )
)
